# H1DR01.net
KiCad netlist of a schematic drawn in EAGLE
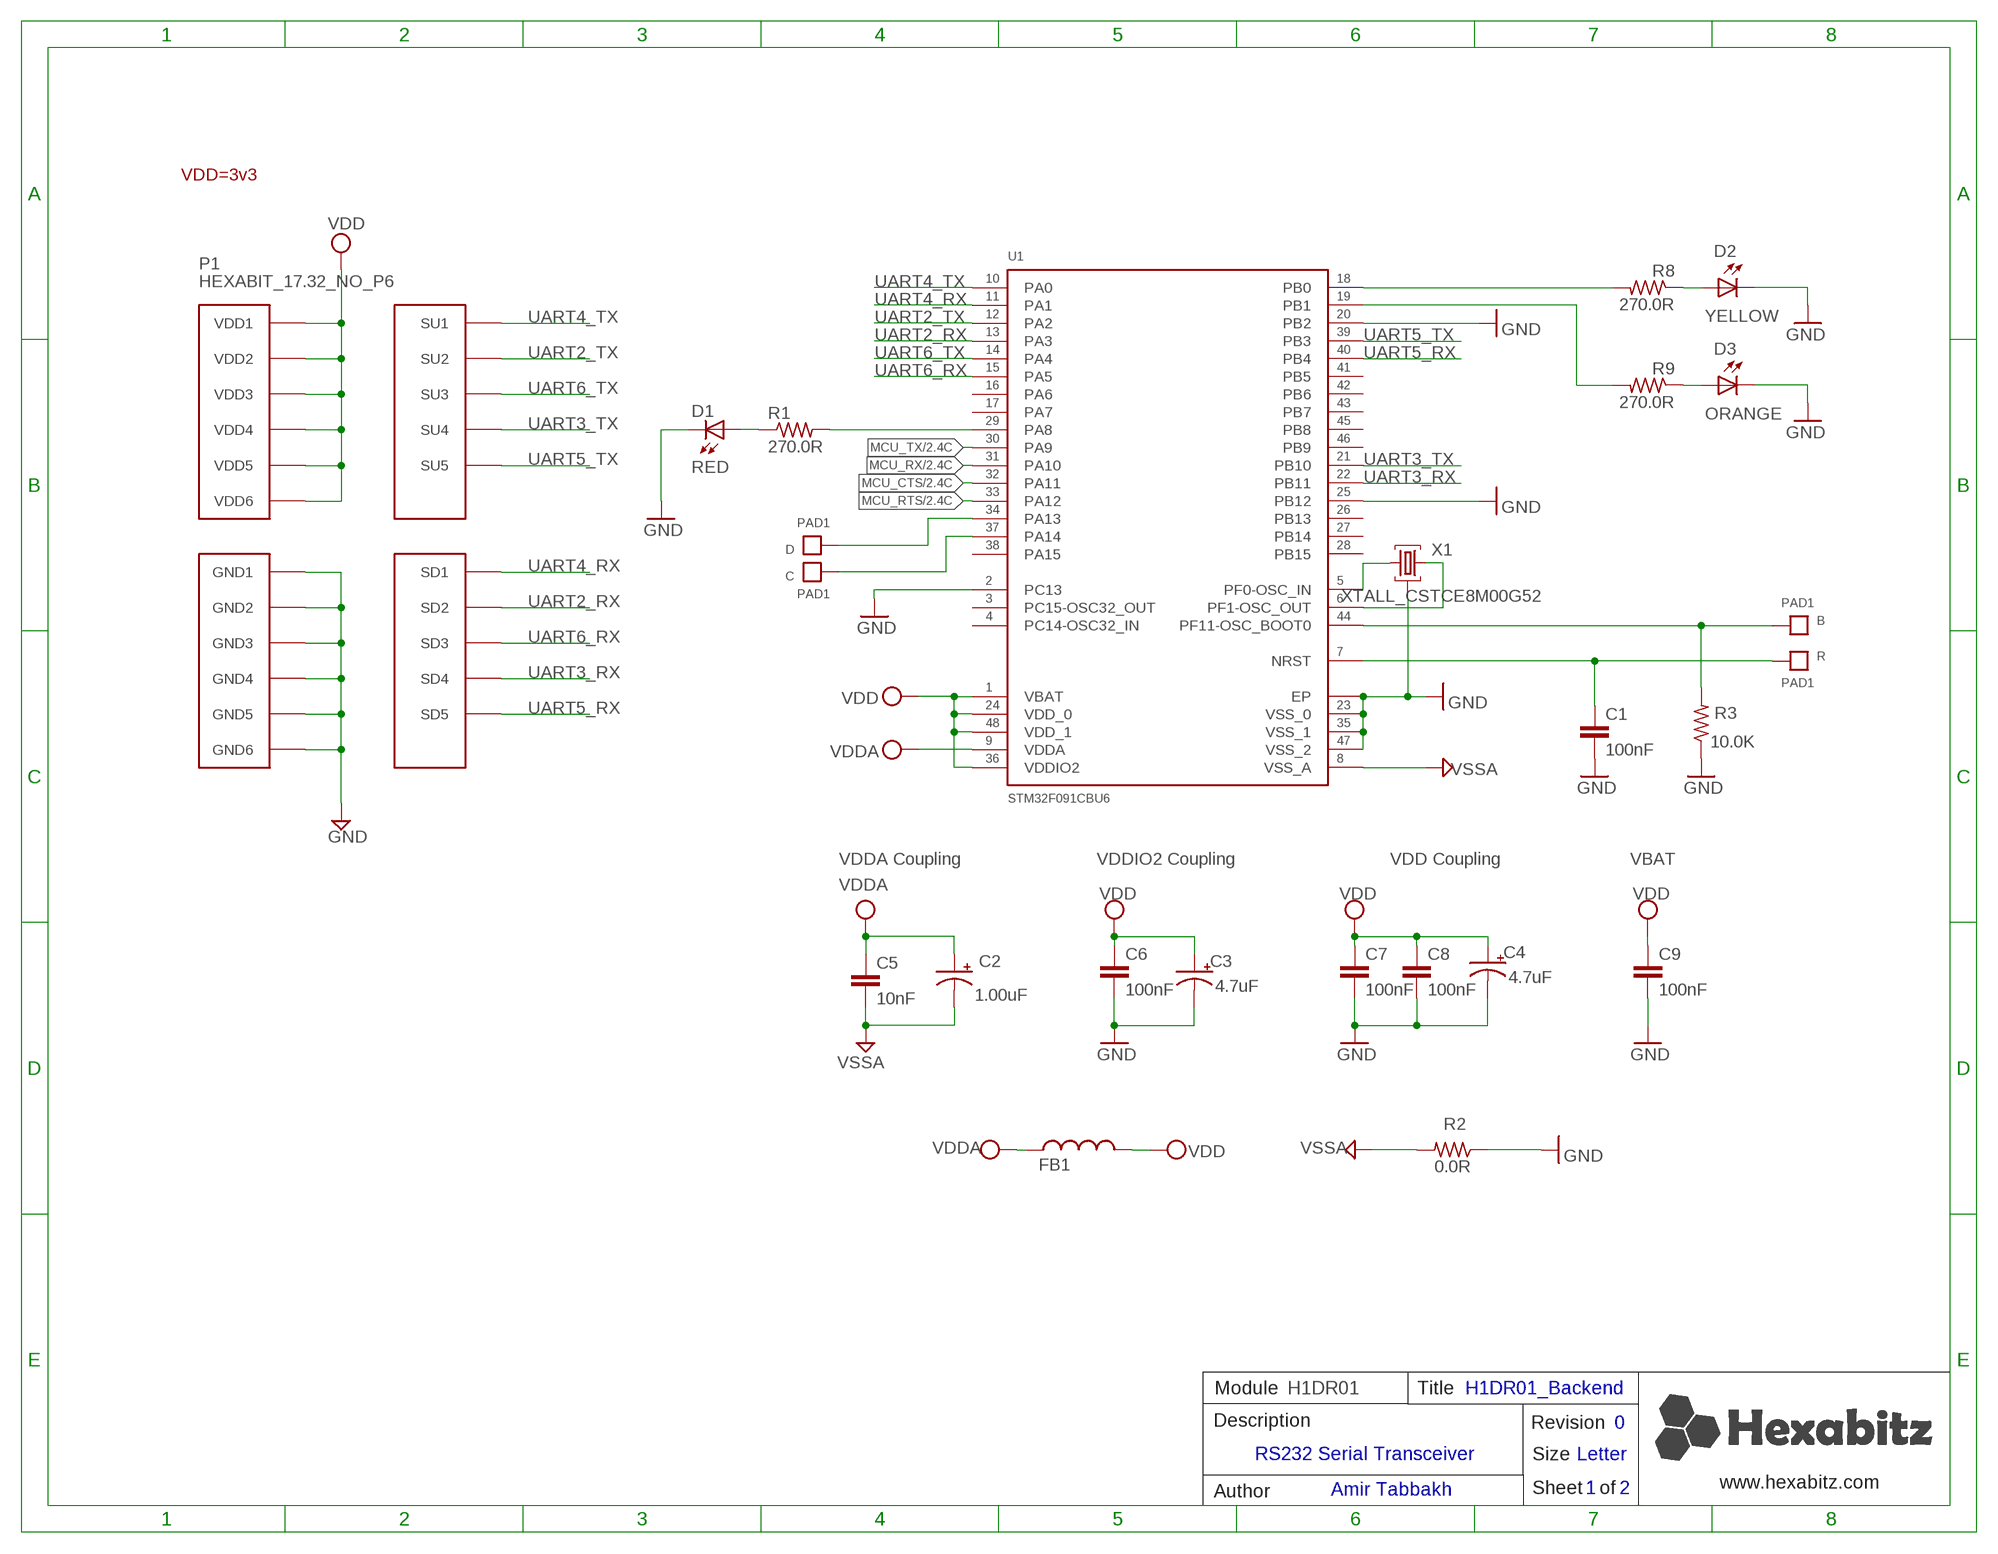
[diagram p0: schematic, sheet 1]
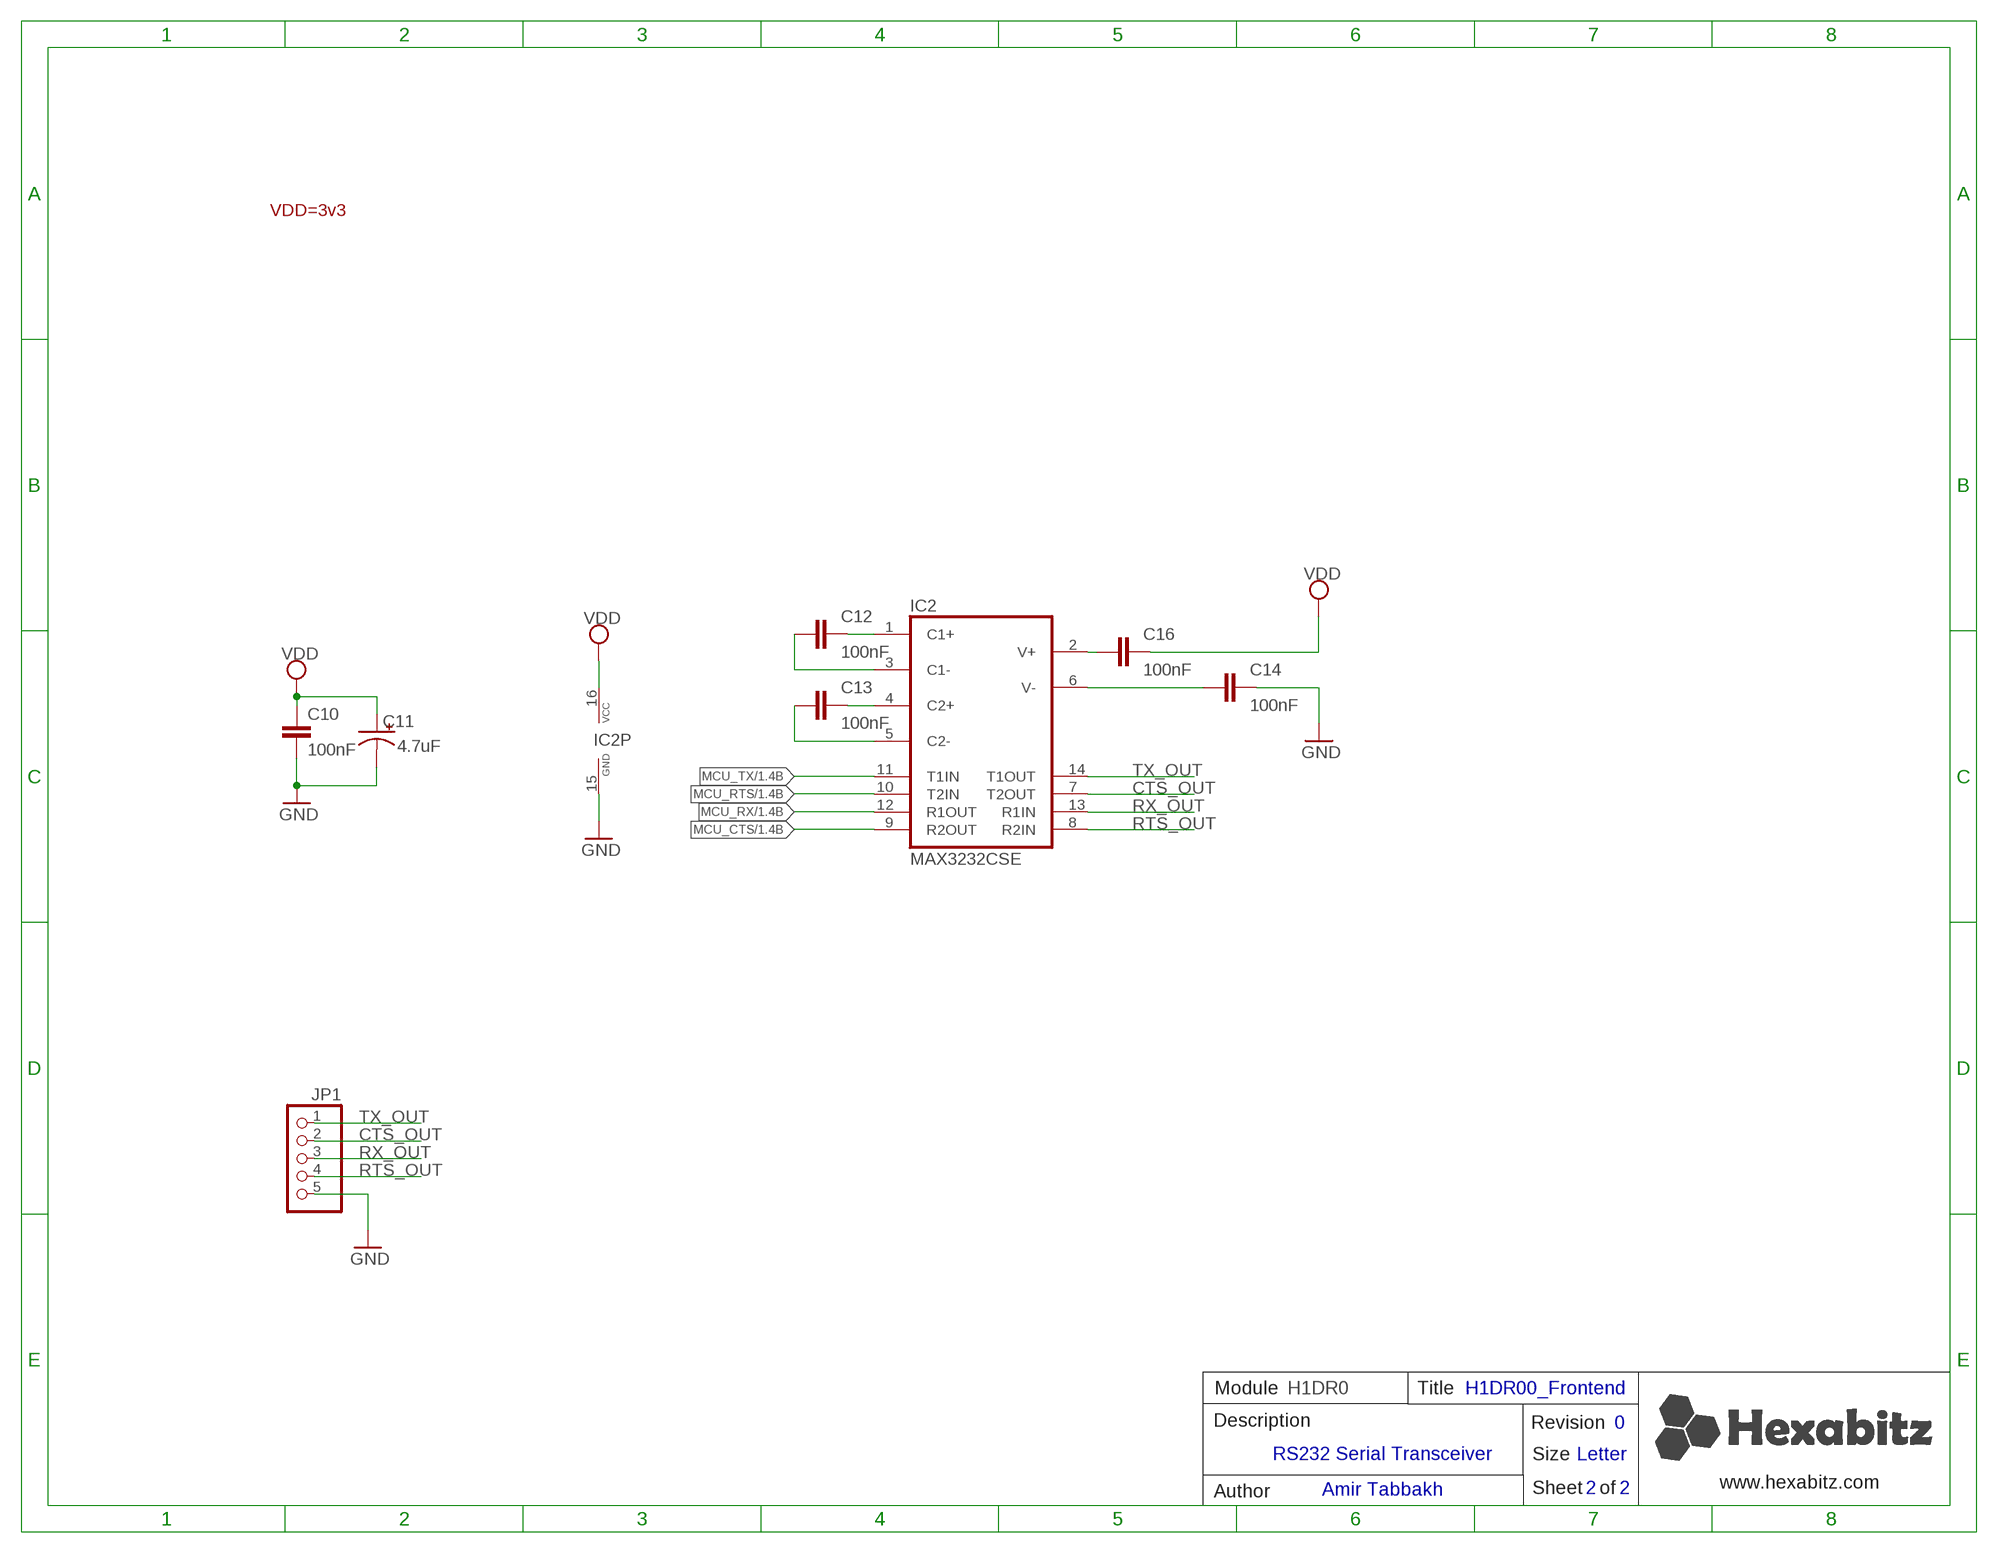
[diagram p1: schematic, sheet 2]

(export (version "E")
  (design (tool "Eeschema 10.0.6"))
  (components
    (comp (ref "B")
      (value "PAD1")
      (footprint "eagle-import:PAD1")
      (libsource (lib "eagle-import") (part "PAD1"))
    )
    (comp (ref "C")
      (value "PAD1")
      (footprint "eagle-import:PAD1")
      (libsource (lib "eagle-import") (part "PAD1"))
    )
    (comp (ref "C1")
      (value "100nF")
      (footprint "eagle-import:C-0603")
      (fields
        (field (name "CAPACITANCE") "100nF")
        (field (name "MFN") "KEMET")
        (field (name "MPN") "C0603C104K8RACTU")
        (field (name "OCTOPART_URL") "https://octopart.com/c0603c104k8ractu-kemet-145075?r=sp&s=9bS9ASSwSEqMCE9KBEQZ0g")
        (field (name "TOLERANCE") "10%")
        (field (name "VOLTAGE_RATING") "10V")
      )
      (libsource (lib "eagle-import") (part "C-0603"))
    )
    (comp (ref "C2")
      (value "1.00uF")
      (footprint "eagle-import:C-0805-POL")
      (fields
        (field (name "CAPACITANCE") "1.00uF")
        (field (name "MFN") "Yageo")
        (field (name "MPN") "CC0805KKX7R7BB105")
        (field (name "OCTOPART_URL") "https://octopart.com/cc0805kkx7r7bb105-yageo-8376555?r=sp&s=YKl1wwtkROau_X5nniH2ig")
        (field (name "TOLERANCE") "10%")
        (field (name "VOLTAGE_RATING") "16V")
      )
      (libsource (lib "eagle-import") (part "C-0805-POL"))
    )
    (comp (ref "C3")
      (value "4.7uF")
      (footprint "eagle-import:C-0805-POL")
      (fields
        (field (name "CAPACITANCE") "4.7uF")
        (field (name "MFN") "Murata")
        (field (name "MPN") "GRM21BC81E475KA12L")
        (field (name "OCTOPART_URL") "https://octopart.com/grm21bc81e475ka12l-murata-10331911?r=sp&s=RY3qZSD8T6mG6TC9CHI5qQ")
        (field (name "TOLERANCE") "10%")
        (field (name "VOLTAGE_RATING") "25V")
      )
      (libsource (lib "eagle-import") (part "C-0805-POL"))
    )
    (comp (ref "C4")
      (value "4.7uF")
      (footprint "eagle-import:C-0805-POL")
      (fields
        (field (name "CAPACITANCE") "4.7uF")
        (field (name "MFN") "Murata")
        (field (name "MPN") "GRM21BC81E475KA12L")
        (field (name "OCTOPART_URL") "https://octopart.com/grm21bc81e475ka12l-murata-10331911?r=sp&s=RY3qZSD8T6mG6TC9CHI5qQ")
        (field (name "TOLERANCE") "10%")
        (field (name "VOLTAGE_RATING") "25V")
      )
      (libsource (lib "eagle-import") (part "C-0805-POL"))
    )
    (comp (ref "C5")
      (value "10nF")
      (footprint "eagle-import:C-0603")
      (fields
        (field (name "CAPACITANCE") "10nF")
        (field (name "MFN") "KEMET")
        (field (name "MPN") "C0603C103K5RACTU")
        (field (name "OCTOPART_URL") "https://octopart.com/c0603c103k5ractu-kemet-133094?r=sp&s=R_iPBxLnSmGqhkU2rIMFpg")
        (field (name "TOLERANCE") "10%")
        (field (name "VOLTAGE_RATING") "50V")
      )
      (libsource (lib "eagle-import") (part "C-0603"))
    )
    (comp (ref "C6")
      (value "100nF")
      (footprint "eagle-import:C-0603")
      (fields
        (field (name "CAPACITANCE") "100nF")
        (field (name "MFN") "KEMET")
        (field (name "MPN") "C0603C104K8RACTU")
        (field (name "OCTOPART_URL") "https://octopart.com/c0603c104k8ractu-kemet-145075?r=sp&s=9bS9ASSwSEqMCE9KBEQZ0g")
        (field (name "TOLERANCE") "10%")
        (field (name "VOLTAGE_RATING") "10V")
      )
      (libsource (lib "eagle-import") (part "C-0603"))
    )
    (comp (ref "C7")
      (value "100nF")
      (footprint "eagle-import:C-0603")
      (fields
        (field (name "CAPACITANCE") "100nF")
        (field (name "MFN") "KEMET")
        (field (name "MPN") "C0603C104K8RACTU")
        (field (name "OCTOPART_URL") "https://octopart.com/c0603c104k8ractu-kemet-145075?r=sp&s=9bS9ASSwSEqMCE9KBEQZ0g")
        (field (name "TOLERANCE") "10%")
        (field (name "VOLTAGE_RATING") "10")
      )
      (libsource (lib "eagle-import") (part "C-0603"))
    )
    (comp (ref "C8")
      (value "100nF")
      (footprint "eagle-import:C-0603")
      (fields
        (field (name "CAPACITANCE") "100nF")
        (field (name "MFN") "KEMET")
        (field (name "MPN") "C0603C104K8RACTU")
        (field (name "OCTOPART_URL") "https://octopart.com/c0603c104k8ractu-kemet-145075?r=sp&s=9bS9ASSwSEqMCE9KBEQZ0g")
        (field (name "TOLERANCE") "10%")
        (field (name "VOLTAGE_RATING") "10V")
      )
      (libsource (lib "eagle-import") (part "C-0603"))
    )
    (comp (ref "C9")
      (value "100nF")
      (footprint "eagle-import:C-0603")
      (fields
        (field (name "CAPACITANCE") "100nF")
        (field (name "MFN") "KEMET")
        (field (name "MPN") "C0603C104K8RACTU")
        (field (name "OCTOPART_URL") "https://octopart.com/c0603c104k8ractu-kemet-145075?r=sp&s=9bS9ASSwSEqMCE9KBEQZ0g")
        (field (name "TOLERANCE") "10V")
        (field (name "VOLTAGE_RATING") "10%")
      )
      (libsource (lib "eagle-import") (part "C-0603"))
    )
    (comp (ref "D")
      (value "PAD1")
      (footprint "eagle-import:PAD1")
      (libsource (lib "eagle-import") (part "PAD1"))
    )
    (comp (ref "D1")
      (value "RED")
      (footprint "eagle-import:VLMS1300-GS08")
      (fields
        (field (name "MPN") "VLMS1300-GS08")
        (field (name "MFN") "Vishay")
        (field (name "MPN_1") "VLMS1300-GS08")
        (field (name "OCTOPART_URL") "https://octopart.com/vlms1300-gs08-vishay-21709201?r=sp&s=_gcP4_q8T1SC6PJQPTQ9yA")
      )
      (libsource (lib "eagle-import") (part "VLMS1300-GS08"))
    )
    (comp (ref "D2")
      (value "YELLOW")
      (footprint "eagle-import:VLMS1300-GS08")
      (fields
        (field (name "MPN") "VLMS1300-GS08")
        (field (name "MFN") "Vishay")
        (field (name "MPN_1") "VLMY1300-GS08")
        (field (name "OCTOPART_URL") "https://octopart.com/vlmy1300-gs08-vishay-21709204?r=sp")
      )
      (libsource (lib "eagle-import") (part "VLMS1300-GS08"))
    )
    (comp (ref "D3")
      (value "ORANGE")
      (footprint "eagle-import:VLMS1300-GS08")
      (fields
        (field (name "MPN") "VLMS1300-GS08")
        (field (name "MFN") "Vishay")
        (field (name "MPN_1") "VLMO1300-GS08 ")
        (field (name "OCTOPART_URL") "https://octopart.com/vlmo1300-gs08-vishay-21709200?r=sp#")
      )
      (libsource (lib "eagle-import") (part "VLMS1300-GS08"))
    )
    (comp (ref "FB1")
      (value "FB-TDK_MMZ1608Y300B")
      (footprint "eagle-import:FB-TDK_MMZ1608Y300B")
      (fields
        (field (name "MFN") "TDK ")
        (field (name "MPN") "MMZ1608Y300B")
        (field (name "OCTOPART_URL") "https://octopart.com/mmz1608y300b-tdk-368280?r=sp&s=cd9_2ZEqQ9q9UNBuQgHAiA")
      )
      (libsource (lib "eagle-import") (part "FB-TDK_MMZ1608Y300B"))
    )
    (comp (ref "P1")
      (value "HEXABIT_17.32_NO_P6")
      (footprint "eagle-import:HEXABIT_17.32_NO_P6")
      (libsource (lib "eagle-import") (part "HEXABIT_?_NO_P617.32"))
    )
    (comp (ref "R")
      (value "PAD1")
      (footprint "eagle-import:PAD1")
      (libsource (lib "eagle-import") (part "PAD1"))
    )
    (comp (ref "R1")
      (value "270.0R")
      (footprint "eagle-import:R-0603")
      (fields
        (field (name "MFN") "Yageo")
        (field (name "MPN") "RC0603FR-07270RL")
        (field (name "OCTOPART_URL") "https://octopart.com/search?q=RC0603FR-07270RL&start=0")
        (field (name "RESISTANCE") "270.0 Ohm")
        (field (name "TOLERANCE") "1%")
      )
      (libsource (lib "eagle-import") (part "R-0603"))
    )
    (comp (ref "R2")
      (value "0.0R")
      (footprint "eagle-import:R-0603")
      (fields
        (field (name "MFN") "Yageo")
        (field (name "MPN") "RC0603JR-070RL")
        (field (name "OCTOPART_URL") "https://octopart.com/rc0603jr-070rl-yageo-1241539?r=sp&s=X2NteqRjRNWrnx42Y0aliA")
        (field (name "RESISTANCE") "0.0 Ohm")
      )
      (libsource (lib "eagle-import") (part "R-0603"))
    )
    (comp (ref "R3")
      (value "10.0K")
      (footprint "eagle-import:R-0603")
      (fields
        (field (name "MFN") "Yageo")
        (field (name "MPN") "RC0603JR-0710KL")
        (field (name "OCTOPART_URL") "https://octopart.com/search?q=RC0603JR-0710KL&start=0")
        (field (name "RESISTANCE") "10.0K Ohm")
        (field (name "TOLERANCE") "5%")
      )
      (libsource (lib "eagle-import") (part "R-0603"))
    )
    (comp (ref "R8")
      (value "270.0R")
      (footprint "eagle-import:R-0603")
      (fields
        (field (name "MFN") "Yageo")
        (field (name "MPN") "RC0603FR-07270RL")
        (field (name "OCTOPART_URL") "https://octopart.com/search?q=RC0603FR-07270RL&start=0")
        (field (name "RESISTANCE") "270.0 Ohm")
        (field (name "TOLERANCE") "1%")
      )
      (libsource (lib "eagle-import") (part "R-0603"))
    )
    (comp (ref "R9")
      (value "270.0R")
      (footprint "eagle-import:R-0603")
      (fields
        (field (name "MFN") "Yageo")
        (field (name "MPN") "RC0603FR-07270RL")
        (field (name "OCTOPART_URL") "https://octopart.com/search?q=RC0603FR-07270RL&start=0")
        (field (name "RESISTANCE") "270.0 Ohm")
        (field (name "TOLERANCE") "1%")
      )
      (libsource (lib "eagle-import") (part "R-0603"))
    )
    (comp (ref "U1")
      (value "STM32F091CBU6")
      (footprint "eagle-import:STM32F091CBU6")
      (libsource (lib "eagle-import") (part "STM32F091CBU6"))
    )
    (comp (ref "X1")
      (value "XTALL_CSTCE8M00G52")
      (footprint "eagle-import:XTALL_CSTCE8M00G52")
      (fields (field (name "MPN") "CSTCE8M00G52Z-R0"))
      (libsource (lib "eagle-import") (part "XTALL_CSTCE8M00G52"))
    )
    (comp (ref "C10")
      (value "100nF")
      (footprint "eagle-import:C-0603")
      (fields
        (field (name "CAPACITANCE") "100nF")
        (field (name "MFN") "KEMET")
        (field (name "MPN") "C0603C104K8RACTU")
        (field (name "OCTOPART_URL") "https://octopart.com/c0603c104k8ractu-kemet-145075?r=sp&s=9bS9ASSwSEqMCE9KBEQZ0g")
        (field (name "TOLERANCE") "10%")
        (field (name "VOLTAGE_RATING") "10V")
      )
      (libsource (lib "eagle-import") (part "C-0603"))
    )
    (comp (ref "C11")
      (value "4.7uF")
      (footprint "eagle-import:C-0805-POL")
      (fields
        (field (name "CAPACITANCE") "4.7uF")
        (field (name "MFN") "Murata")
        (field (name "MPN") "GRM21BC81E475KA12L")
        (field (name "OCTOPART_URL") "https://octopart.com/grm21bc81e475ka12l-murata-10331911?r=sp&s=RY3qZSD8T6mG6TC9CHI5qQ")
        (field (name "TOLERANCE") "10%")
        (field (name "VOLTAGE_RATING") "25V")
      )
      (libsource (lib "eagle-import") (part "C-0805-POL"))
    )
    (comp (ref "C12")
      (value "100nF")
      (footprint "eagle-import:C-0603")
      (fields
        (field (name "CAPACITANCE") "100nF")
        (field (name "MFN") "KEMET")
        (field (name "MPN") "C0603C104K8RACTU")
        (field (name "OCTOPART_URL") "https://octopart.com/c0603c104k8ractu-kemet-145075?r=sp&s=9bS9ASSwSEqMCE9KBEQZ0g")
        (field (name "TOLERANCE") "10%")
        (field (name "VOLTAGE_RATING") "10")
      )
      (libsource (lib "eagle-import") (part "C-0603"))
    )
    (comp (ref "C13")
      (value "100nF")
      (footprint "eagle-import:C-0603")
      (fields
        (field (name "CAPACITANCE") "100nF")
        (field (name "MFN") "KEMET")
        (field (name "MPN") "C0603C104K8RACTU")
        (field (name "OCTOPART_URL") "https://octopart.com/c0603c104k8ractu-kemet-145075?r=sp&s=9bS9ASSwSEqMCE9KBEQZ0g")
        (field (name "TOLERANCE") "10%")
        (field (name "VOLTAGE_RATING") "10")
      )
      (libsource (lib "eagle-import") (part "C-0603"))
    )
    (comp (ref "C14")
      (value "100nF")
      (footprint "eagle-import:C-0603")
      (fields
        (field (name "CAPACITANCE") "100nF")
        (field (name "MFN") "KEMET")
        (field (name "MPN") "C0603C104K8RACTU")
        (field (name "OCTOPART_URL") "https://octopart.com/c0603c104k8ractu-kemet-145075?r=sp&s=9bS9ASSwSEqMCE9KBEQZ0g")
        (field (name "TOLERANCE") "10%")
        (field (name "VOLTAGE_RATING") "10")
      )
      (libsource (lib "eagle-import") (part "C-0603"))
    )
    (comp (ref "C16")
      (value "100nF")
      (footprint "eagle-import:C-0603")
      (fields
        (field (name "CAPACITANCE") "100nF")
        (field (name "MFN") "KEMET")
        (field (name "MPN") "C0603C104K8RACTU")
        (field (name "OCTOPART_URL") "https://octopart.com/c0603c104k8ractu-kemet-145075?r=sp&s=9bS9ASSwSEqMCE9KBEQZ0g")
        (field (name "TOLERANCE") "10%")
        (field (name "VOLTAGE_RATING") "10")
      )
      (libsource (lib "eagle-import") (part "C-0603"))
    )
    (comp (ref "IC2")
      (value "MAX3232CSE")
      (footprint "eagle-import:SO16")
      (description "MAX3232 Series 235 kbps 5.5 V Surface Mount RS-232 Transceiver - SOIC-16")
      (fields
        (field (name "MFN") "Maxim Integrated")
        (field (name "OCTOPART_URL") "https://octopart.com/max3232cse%2B-maxim+integrated-39430845?r=sp")
      )
      (libsource (lib "eagle-import") (part "MAX3232SEC"))
    )
    (comp (ref "JP1")
      (value "PINHD-1X5/90")
      (footprint "eagle-import:1X05_90")
      (description "Conn Header R/a 5POS 2.54MM MALE")
      (fields (field (name "MPN") "PEC05SBAN"))
      (libsource (lib "eagle-import") (part "PINHD-1X5/90"))
    )
  )
  (nets
    (net (code "1") (name "CTS_OUT") (class "Default")
      (node (ref "IC2") (pin "7") (pinfunction "T2OUT_7") (pintype "output"))
      (node (ref "JP1") (pin "2") (pinfunction "2_2") (pintype "passive"))
    )
    (net (code "2") (name "GND") (class "Default")
      (node (ref "C1") (pin "2") (pinfunction "2_2") (pintype "passive"))
      (node (ref "C10") (pin "2") (pinfunction "2_2") (pintype "passive"))
      (node (ref "C11") (pin "2") (pinfunction "-_2") (pintype "passive"))
      (node (ref "C14") (pin "2") (pinfunction "2_2") (pintype "passive"))
      (node (ref "C3") (pin "2") (pinfunction "-_2") (pintype "passive"))
      (node (ref "C4") (pin "2") (pinfunction "-_2") (pintype "passive"))
      (node (ref "C6") (pin "2") (pinfunction "2_2") (pintype "passive"))
      (node (ref "C7") (pin "2") (pinfunction "2_2") (pintype "passive"))
      (node (ref "C8") (pin "2") (pinfunction "2_2") (pintype "passive"))
      (node (ref "C9") (pin "2") (pinfunction "2_2") (pintype "passive"))
      (node (ref "D1") (pin "C") (pinfunction "C_C") (pintype "passive"))
      (node (ref "D2") (pin "C") (pinfunction "C_C") (pintype "passive"))
      (node (ref "D3") (pin "C") (pinfunction "C_C") (pintype "passive"))
      (node (ref "IC2") (pin "15") (pinfunction "GND_15") (pintype "power_in"))
      (node (ref "JP1") (pin "5") (pinfunction "5_5") (pintype "passive"))
      (node (ref "P1") (pin "PAD_PD10") (pinfunction "GND4_PAD_PD10") (pintype "power_in"))
      (node (ref "P1") (pin "PAD_PD11") (pinfunction "GND5_PAD_PD11") (pintype "power_in"))
      (node (ref "P1") (pin "PAD_PD12") (pinfunction "GND6_PAD_PD12") (pintype "power_in"))
      (node (ref "P1") (pin "PAD_PD7") (pinfunction "GND1_PAD_PD7") (pintype "power_in"))
      (node (ref "P1") (pin "PAD_PD8") (pinfunction "GND2_PAD_PD8") (pintype "power_in"))
      (node (ref "P1") (pin "PAD_PD9") (pinfunction "GND3_PAD_PD9") (pintype "power_in"))
      (node (ref "R2") (pin "1") (pinfunction "1_1") (pintype "passive"))
      (node (ref "R3") (pin "1") (pinfunction "1_1") (pintype "passive"))
      (node (ref "U1") (pin "EP") (pinfunction "EP_EP") (pintype "power_in"))
      (node (ref "U1") (pin "P$2") (pinfunction "PC13_P$2") (pintype "bidirectional"))
      (node (ref "U1") (pin "P$20") (pinfunction "PB2_P$20") (pintype "bidirectional"))
      (node (ref "U1") (pin "P$23") (pinfunction "VSS_0_P$23") (pintype "power_in"))
      (node (ref "U1") (pin "P$25") (pinfunction "PB12_P$25") (pintype "bidirectional"))
      (node (ref "U1") (pin "P$35") (pinfunction "VSS_1_P$35") (pintype "power_in"))
      (node (ref "U1") (pin "P$47") (pinfunction "VSS_2_P$47") (pintype "power_in"))
      (node (ref "X1") (pin "P$2") (pinfunction "2_P$2") (pintype "passive"))
    )
    (net (code "3") (name "MCU_CTS") (class "Default")
      (node (ref "IC2") (pin "9") (pinfunction "R2OUT_9") (pintype "output"))
      (node (ref "U1") (pin "P$32") (pinfunction "PA11_P$32") (pintype "bidirectional"))
    )
    (net (code "4") (name "MCU_RTS") (class "Default")
      (node (ref "IC2") (pin "10") (pinfunction "T2IN_10") (pintype "input"))
      (node (ref "U1") (pin "P$33") (pinfunction "PA12_P$33") (pintype "bidirectional"))
    )
    (net (code "5") (name "MCU_RX") (class "Default")
      (node (ref "IC2") (pin "12") (pinfunction "R1OUT_12") (pintype "output"))
      (node (ref "U1") (pin "P$31") (pinfunction "PA10_P$31") (pintype "bidirectional"))
    )
    (net (code "6") (name "MCU_TX") (class "Default")
      (node (ref "IC2") (pin "11") (pinfunction "T1IN_11") (pintype "input"))
      (node (ref "U1") (pin "P$30") (pinfunction "PA9_P$30") (pintype "bidirectional"))
    )
    (net (code "7") (name "Net-(D1-PadA)") (class "Default")
      (node (ref "D1") (pin "A") (pinfunction "A_A") (pintype "passive"))
      (node (ref "R1") (pin "1") (pinfunction "1_1") (pintype "passive"))
    )
    (net (code "8") (name "Net-(D2-PadA)") (class "Default")
      (node (ref "D2") (pin "A") (pinfunction "A_A") (pintype "passive"))
      (node (ref "R8") (pin "1") (pinfunction "1_1") (pintype "passive"))
    )
    (net (code "9") (name "Net-(D3-PadA)") (class "Default")
      (node (ref "D3") (pin "A") (pinfunction "A_A") (pintype "passive"))
      (node (ref "R9") (pin "1") (pinfunction "1_1") (pintype "passive"))
    )
    (net (code "10") (name "Net-(IC2A-C1+)") (class "Default")
      (node (ref "C12") (pin "2") (pinfunction "2_2") (pintype "passive"))
      (node (ref "IC2") (pin "1") (pinfunction "C1+_1") (pintype "bidirectional"))
    )
    (net (code "11") (name "Net-(IC2A-C1-)") (class "Default")
      (node (ref "C12") (pin "1") (pinfunction "1_1") (pintype "passive"))
      (node (ref "IC2") (pin "3") (pinfunction "C1-_3") (pintype "bidirectional"))
    )
    (net (code "12") (name "Net-(IC2A-C2+)") (class "Default")
      (node (ref "C13") (pin "2") (pinfunction "2_2") (pintype "passive"))
      (node (ref "IC2") (pin "4") (pinfunction "C2+_4") (pintype "bidirectional"))
    )
    (net (code "13") (name "Net-(IC2A-C2-)") (class "Default")
      (node (ref "C13") (pin "1") (pinfunction "1_1") (pintype "passive"))
      (node (ref "IC2") (pin "5") (pinfunction "C2-_5") (pintype "bidirectional"))
    )
    (net (code "14") (name "Net-(IC2A-V+)") (class "Default")
      (node (ref "C16") (pin "1") (pinfunction "1_1") (pintype "passive"))
      (node (ref "IC2") (pin "2") (pinfunction "V+_2") (pintype "bidirectional"))
    )
    (net (code "15") (name "Net-(IC2A-V-)") (class "Default")
      (node (ref "C14") (pin "1") (pinfunction "1_1") (pintype "passive"))
      (node (ref "IC2") (pin "6") (pinfunction "V-_6") (pintype "bidirectional"))
    )
    (net (code "16") (name "Net-(U1-NRST)") (class "Default")
      (node (ref "C1") (pin "1") (pinfunction "1_1") (pintype "passive"))
      (node (ref "R") (pin "P$1") (pinfunction "P$1_P$1") (pintype "passive"))
      (node (ref "R") (pin "P$2") (pinfunction "P$1_P$2") (pintype "passive"))
      (node (ref "U1") (pin "P$7") (pinfunction "NRST_P$7") (pintype "passive"))
    )
    (net (code "17") (name "Net-(U1-PA8)") (class "Default")
      (node (ref "R1") (pin "2") (pinfunction "2_2") (pintype "passive"))
      (node (ref "U1") (pin "P$29") (pinfunction "PA8_P$29") (pintype "bidirectional"))
    )
    (net (code "18") (name "Net-(U1-PA13)") (class "Default")
      (node (ref "D") (pin "P$1") (pinfunction "P$1_P$1") (pintype "passive"))
      (node (ref "D") (pin "P$2") (pinfunction "P$1_P$2") (pintype "passive"))
      (node (ref "U1") (pin "P$34") (pinfunction "PA13_P$34") (pintype "bidirectional"))
    )
    (net (code "19") (name "Net-(U1-PA14)") (class "Default")
      (node (ref "C") (pin "P$1") (pinfunction "P$1_P$1") (pintype "passive"))
      (node (ref "C") (pin "P$2") (pinfunction "P$1_P$2") (pintype "passive"))
      (node (ref "U1") (pin "P$37") (pinfunction "PA14_P$37") (pintype "bidirectional"))
    )
    (net (code "20") (name "Net-(U1-PB0)") (class "Default")
      (node (ref "R8") (pin "2") (pinfunction "2_2") (pintype "passive"))
      (node (ref "U1") (pin "P$18") (pinfunction "PB0_P$18") (pintype "bidirectional"))
    )
    (net (code "21") (name "Net-(U1-PB1)") (class "Default")
      (node (ref "R9") (pin "2") (pinfunction "2_2") (pintype "passive"))
      (node (ref "U1") (pin "P$19") (pinfunction "PB1_P$19") (pintype "bidirectional"))
    )
    (net (code "22") (name "Net-(U1-PF0-OSC_IN)") (class "Default")
      (node (ref "U1") (pin "P$5") (pinfunction "PF0-OSC_IN_P$5") (pintype "bidirectional"))
      (node (ref "X1") (pin "P$1") (pinfunction "1_P$1") (pintype "passive"))
    )
    (net (code "23") (name "Net-(U1-PF1-OSC_OUT)") (class "Default")
      (node (ref "U1") (pin "P$6") (pinfunction "PF1-OSC_OUT_P$6") (pintype "bidirectional"))
      (node (ref "X1") (pin "P$3") (pinfunction "3_P$3") (pintype "passive"))
    )
    (net (code "24") (name "Net-(U1-PF11-OSC_BOOT0)") (class "Default")
      (node (ref "B") (pin "P$1") (pinfunction "P$1_P$1") (pintype "passive"))
      (node (ref "B") (pin "P$2") (pinfunction "P$1_P$2") (pintype "passive"))
      (node (ref "R3") (pin "2") (pinfunction "2_2") (pintype "passive"))
      (node (ref "U1") (pin "P$44") (pinfunction "PF11-OSC_BOOT0_P$44") (pintype "bidirectional"))
    )
    (net (code "25") (name "RTS_OUT") (class "Default")
      (node (ref "IC2") (pin "8") (pinfunction "R2IN_8") (pintype "input"))
      (node (ref "JP1") (pin "4") (pinfunction "4_4") (pintype "passive"))
    )
    (net (code "26") (name "RX_OUT") (class "Default")
      (node (ref "IC2") (pin "13") (pinfunction "R1IN_13") (pintype "input"))
      (node (ref "JP1") (pin "3") (pinfunction "3_3") (pintype "passive"))
    )
    (net (code "27") (name "TX_OUT") (class "Default")
      (node (ref "IC2") (pin "14") (pinfunction "T1OUT_14") (pintype "output"))
      (node (ref "JP1") (pin "1") (pinfunction "1_1") (pintype "passive"))
    )
    (net (code "28") (name "UART2_RX") (class "Default")
      (node (ref "P1") (pin "PAD_PD2") (pinfunction "SD2_PAD_PD2") (pintype "bidirectional"))
      (node (ref "U1") (pin "P$13") (pinfunction "PA3_P$13") (pintype "bidirectional"))
    )
    (net (code "29") (name "UART2_TX") (class "Default")
      (node (ref "P1") (pin "PAD_PU2") (pinfunction "SU2_PAD_PU2") (pintype "bidirectional"))
      (node (ref "U1") (pin "P$12") (pinfunction "PA2_P$12") (pintype "bidirectional"))
    )
    (net (code "30") (name "UART3_RX") (class "Default")
      (node (ref "P1") (pin "PAD_PD4") (pinfunction "SD4_PAD_PD4") (pintype "bidirectional"))
      (node (ref "U1") (pin "P$22") (pinfunction "PB11_P$22") (pintype "bidirectional"))
    )
    (net (code "31") (name "UART3_TX") (class "Default")
      (node (ref "P1") (pin "PAD_PU4") (pinfunction "SU4_PAD_PU4") (pintype "bidirectional"))
      (node (ref "U1") (pin "P$21") (pinfunction "PB10_P$21") (pintype "bidirectional"))
    )
    (net (code "32") (name "UART4_RX") (class "Default")
      (node (ref "P1") (pin "PAD_PD1") (pinfunction "SD1_PAD_PD1") (pintype "bidirectional"))
      (node (ref "U1") (pin "P$11") (pinfunction "PA1_P$11") (pintype "bidirectional"))
    )
    (net (code "33") (name "UART4_TX") (class "Default")
      (node (ref "P1") (pin "PAD_PU1") (pinfunction "SU1_PAD_PU1") (pintype "bidirectional"))
      (node (ref "U1") (pin "P$10") (pinfunction "PA0_P$10") (pintype "bidirectional"))
    )
    (net (code "34") (name "UART5_RX") (class "Default")
      (node (ref "P1") (pin "PAD_PD5") (pinfunction "SD5_PAD_PD5") (pintype "bidirectional"))
      (node (ref "U1") (pin "P$40") (pinfunction "PB4_P$40") (pintype "bidirectional"))
    )
    (net (code "35") (name "UART5_TX") (class "Default")
      (node (ref "P1") (pin "PAD_PU5") (pinfunction "SU5_PAD_PU5") (pintype "bidirectional"))
      (node (ref "U1") (pin "P$39") (pinfunction "PB3_P$39") (pintype "bidirectional"))
    )
    (net (code "36") (name "UART6_RX") (class "Default")
      (node (ref "P1") (pin "PAD_PD3") (pinfunction "SD3_PAD_PD3") (pintype "bidirectional"))
      (node (ref "U1") (pin "P$15") (pinfunction "PA5_P$15") (pintype "bidirectional"))
    )
    (net (code "37") (name "UART6_TX") (class "Default")
      (node (ref "P1") (pin "PAD_PU3") (pinfunction "SU3_PAD_PU3") (pintype "bidirectional"))
      (node (ref "U1") (pin "P$14") (pinfunction "PA4_P$14") (pintype "bidirectional"))
    )
    (net (code "38") (name "VDD") (class "Default")
      (node (ref "C10") (pin "1") (pinfunction "1_1") (pintype "passive"))
      (node (ref "C11") (pin "1") (pinfunction "+_1") (pintype "passive"))
      (node (ref "C16") (pin "2") (pinfunction "2_2") (pintype "passive"))
      (node (ref "C3") (pin "1") (pinfunction "+_1") (pintype "passive"))
      (node (ref "C4") (pin "1") (pinfunction "+_1") (pintype "passive"))
      (node (ref "C6") (pin "1") (pinfunction "1_1") (pintype "passive"))
      (node (ref "C7") (pin "1") (pinfunction "1_1") (pintype "passive"))
      (node (ref "C8") (pin "1") (pinfunction "1_1") (pintype "passive"))
      (node (ref "C9") (pin "1") (pinfunction "1_1") (pintype "passive"))
      (node (ref "FB1") (pin "2") (pinfunction "2_2") (pintype "passive"))
      (node (ref "IC2") (pin "16") (pinfunction "VCC_16") (pintype "power_in"))
      (node (ref "P1") (pin "PAD_PU10") (pinfunction "VDD4_PAD_PU10") (pintype "power_in"))
      (node (ref "P1") (pin "PAD_PU11") (pinfunction "VDD5_PAD_PU11") (pintype "power_in"))
      (node (ref "P1") (pin "PAD_PU12") (pinfunction "VDD6_PAD_PU12") (pintype "power_in"))
      (node (ref "P1") (pin "PAD_PU7") (pinfunction "VDD1_PAD_PU7") (pintype "power_in"))
      (node (ref "P1") (pin "PAD_PU8") (pinfunction "VDD2_PAD_PU8") (pintype "power_in"))
      (node (ref "P1") (pin "PAD_PU9") (pinfunction "VDD3_PAD_PU9") (pintype "power_in"))
      (node (ref "U1") (pin "P$1") (pinfunction "VBAT_P$1") (pintype "power_in"))
      (node (ref "U1") (pin "P$24") (pinfunction "VDD_0_P$24") (pintype "power_in"))
      (node (ref "U1") (pin "P$36") (pinfunction "VDDIO2_P$36") (pintype "power_in"))
      (node (ref "U1") (pin "P$48") (pinfunction "VDD_1_P$48") (pintype "power_in"))
    )
    (net (code "39") (name "VDDA") (class "Default")
      (node (ref "C2") (pin "1") (pinfunction "+_1") (pintype "passive"))
      (node (ref "C5") (pin "1") (pinfunction "1_1") (pintype "passive"))
      (node (ref "FB1") (pin "1") (pinfunction "1_1") (pintype "passive"))
      (node (ref "U1") (pin "P$9") (pinfunction "VDDA_P$9") (pintype "power_in"))
    )
    (net (code "40") (name "VSSA") (class "Default")
      (node (ref "C2") (pin "2") (pinfunction "-_2") (pintype "passive"))
      (node (ref "C5") (pin "2") (pinfunction "2_2") (pintype "passive"))
      (node (ref "R2") (pin "2") (pinfunction "2_2") (pintype "passive"))
      (node (ref "U1") (pin "P$8") (pinfunction "VSS_A_P$8") (pintype "power_in"))
    )
    (net (code "41") (name "unconnected-(U1-PA6-PadP$16)") (class "Default")
      (node (ref "U1") (pin "P$16") (pinfunction "PA6_P$16") (pintype "bidirectional"))
    )
    (net (code "42") (name "unconnected-(U1-PA7-PadP$17)") (class "Default")
      (node (ref "U1") (pin "P$17") (pinfunction "PA7_P$17") (pintype "bidirectional"))
    )
    (net (code "43") (name "unconnected-(U1-PA15-PadP$38)") (class "Default")
      (node (ref "U1") (pin "P$38") (pinfunction "PA15_P$38") (pintype "bidirectional"))
    )
    (net (code "44") (name "unconnected-(U1-PB5-PadP$41)") (class "Default")
      (node (ref "U1") (pin "P$41") (pinfunction "PB5_P$41") (pintype "bidirectional"))
    )
    (net (code "45") (name "unconnected-(U1-PB6-PadP$42)") (class "Default")
      (node (ref "U1") (pin "P$42") (pinfunction "PB6_P$42") (pintype "bidirectional"))
    )
    (net (code "46") (name "unconnected-(U1-PB7-PadP$43)") (class "Default")
      (node (ref "U1") (pin "P$43") (pinfunction "PB7_P$43") (pintype "bidirectional"))
    )
    (net (code "47") (name "unconnected-(U1-PB8-PadP$45)") (class "Default")
      (node (ref "U1") (pin "P$45") (pinfunction "PB8_P$45") (pintype "bidirectional"))
    )
    (net (code "48") (name "unconnected-(U1-PB9-PadP$46)") (class "Default")
      (node (ref "U1") (pin "P$46") (pinfunction "PB9_P$46") (pintype "bidirectional"))
    )
    (net (code "49") (name "unconnected-(U1-PB13-PadP$26)") (class "Default")
      (node (ref "U1") (pin "P$26") (pinfunction "PB13_P$26") (pintype "bidirectional"))
    )
    (net (code "50") (name "unconnected-(U1-PB14-PadP$27)") (class "Default")
      (node (ref "U1") (pin "P$27") (pinfunction "PB14_P$27") (pintype "bidirectional"))
    )
    (net (code "51") (name "unconnected-(U1-PB15-PadP$28)") (class "Default")
      (node (ref "U1") (pin "P$28") (pinfunction "PB15_P$28") (pintype "bidirectional"))
    )
    (net (code "52") (name "unconnected-(U1-PC14-OSC32_IN-PadP$3)") (class "Default")
      (node (ref "U1") (pin "P$3") (pinfunction "PC14-OSC32_IN_P$3") (pintype "bidirectional"))
    )
    (net (code "53") (name "unconnected-(U1-PC15-OSC32_OUT-PadP$4)") (class "Default")
      (node (ref "U1") (pin "P$4") (pinfunction "PC15-OSC32_OUT_P$4") (pintype "bidirectional"))
    )
  )
)
